# Adafruit_NeoPixel_Ring_12.net
KiCad netlist of a schematic drawn in EAGLE
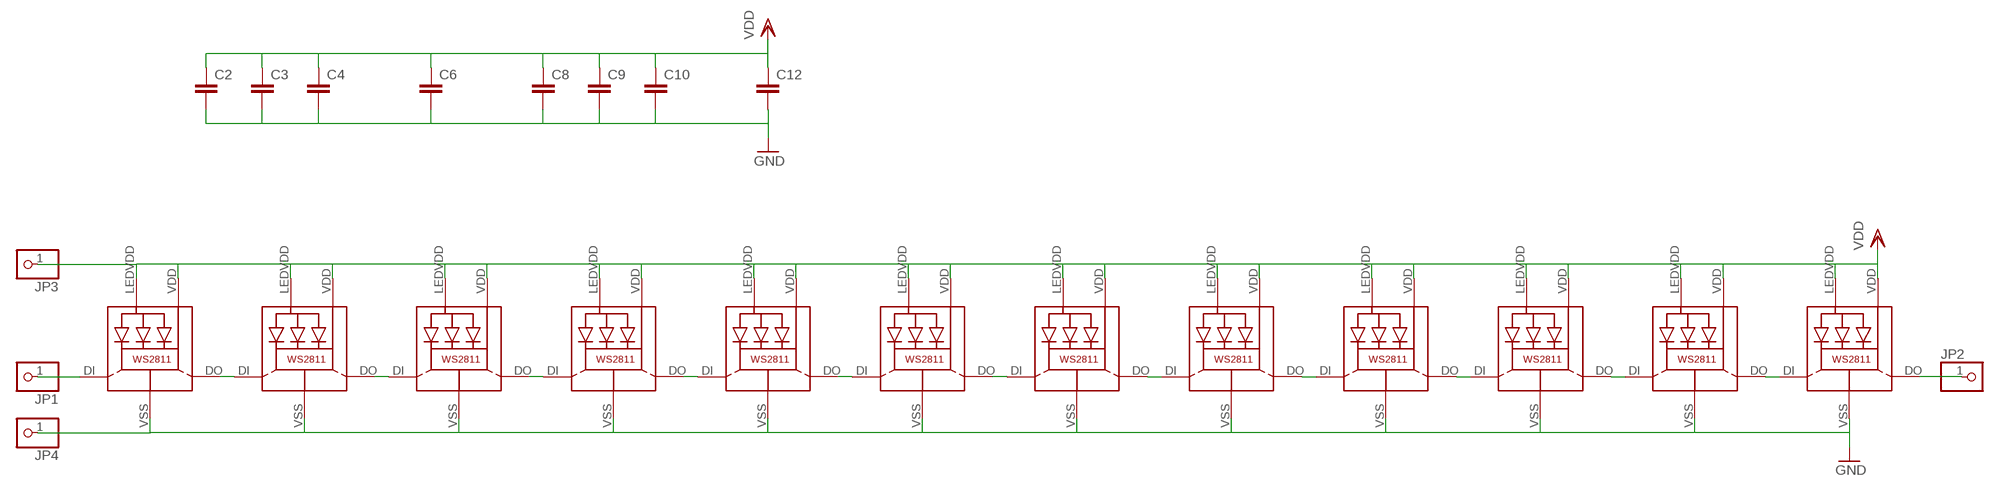
[diagram p0: schematic, sheet 1]

(export (version "E")
  (design (tool "Eeschema 10.0.6"))
  (components
    (comp (ref "C2")
      (value "C-EUC0603")
      (footprint "eagle-import:C0603")
      (libsource (lib "eagle-import") (part "C-EUC0603"))
    )
    (comp (ref "C3")
      (value "C-EUC0603")
      (footprint "eagle-import:C0603")
      (libsource (lib "eagle-import") (part "C-EUC0603"))
    )
    (comp (ref "C4")
      (value "C-EUC0603")
      (footprint "eagle-import:C0603")
      (libsource (lib "eagle-import") (part "C-EUC0603"))
    )
    (comp (ref "C6")
      (value "C-EUC0603")
      (footprint "eagle-import:C0603")
      (libsource (lib "eagle-import") (part "C-EUC0603"))
    )
    (comp (ref "C8")
      (value "C-EUC0603")
      (footprint "eagle-import:C0603")
      (libsource (lib "eagle-import") (part "C-EUC0603"))
    )
    (comp (ref "C9")
      (value "C-EUC0603")
      (footprint "eagle-import:C0603")
      (libsource (lib "eagle-import") (part "C-EUC0603"))
    )
    (comp (ref "C10")
      (value "C-EUC0603")
      (footprint "eagle-import:C0603")
      (libsource (lib "eagle-import") (part "C-EUC0603"))
    )
    (comp (ref "C12")
      (value "C-EUC0603")
      (footprint "eagle-import:C0603")
      (libsource (lib "eagle-import") (part "C-EUC0603"))
    )
    (comp (ref "JP1")
      (value "PINHD-1X1CB")
      (footprint "eagle-import:1X01-CLEANBIG")
      (libsource (lib "eagle-import") (part "PINHD-1X1CB"))
    )
    (comp (ref "JP2")
      (value "PINHD-1X1CB")
      (footprint "eagle-import:1X01-CLEANBIG")
      (libsource (lib "eagle-import") (part "PINHD-1X1CB"))
    )
    (comp (ref "JP3")
      (value "PINHD-1X1CB")
      (footprint "eagle-import:1X01-CLEANBIG")
      (libsource (lib "eagle-import") (part "PINHD-1X1CB"))
    )
    (comp (ref "JP4")
      (value "PINHD-1X1CB")
      (footprint "eagle-import:1X01-CLEANBIG")
      (libsource (lib "eagle-import") (part "PINHD-1X1CB"))
    )
    (comp (ref "LED1")
      (value "WS28115050")
      (footprint "eagle-import:WS28115050")
      (libsource (lib "eagle-import") (part "WS28115050"))
    )
    (comp (ref "LED2")
      (value "WS28115050")
      (footprint "eagle-import:WS28115050")
      (libsource (lib "eagle-import") (part "WS28115050"))
    )
    (comp (ref "LED3")
      (value "WS28115050")
      (footprint "eagle-import:WS28115050")
      (libsource (lib "eagle-import") (part "WS28115050"))
    )
    (comp (ref "LED4")
      (value "WS28115050")
      (footprint "eagle-import:WS28115050")
      (libsource (lib "eagle-import") (part "WS28115050"))
    )
    (comp (ref "LED5")
      (value "WS28115050")
      (footprint "eagle-import:WS28115050")
      (libsource (lib "eagle-import") (part "WS28115050"))
    )
    (comp (ref "LED6")
      (value "WS28115050")
      (footprint "eagle-import:WS28115050")
      (libsource (lib "eagle-import") (part "WS28115050"))
    )
    (comp (ref "LED7")
      (value "WS28115050")
      (footprint "eagle-import:WS28115050")
      (libsource (lib "eagle-import") (part "WS28115050"))
    )
    (comp (ref "LED8")
      (value "WS28115050")
      (footprint "eagle-import:WS28115050")
      (libsource (lib "eagle-import") (part "WS28115050"))
    )
    (comp (ref "LED9")
      (value "WS28115050")
      (footprint "eagle-import:WS28115050")
      (libsource (lib "eagle-import") (part "WS28115050"))
    )
    (comp (ref "LED10")
      (value "WS28115050")
      (footprint "eagle-import:WS28115050")
      (libsource (lib "eagle-import") (part "WS28115050"))
    )
    (comp (ref "LED11")
      (value "WS28115050")
      (footprint "eagle-import:WS28115050")
      (libsource (lib "eagle-import") (part "WS28115050"))
    )
    (comp (ref "LED12")
      (value "WS28115050")
      (footprint "eagle-import:WS28115050")
      (libsource (lib "eagle-import") (part "WS28115050"))
    )
  )
  (nets
    (net (code "1") (name "GND") (class "Default")
      (node (ref "C10") (pin "2") (pinfunction "2_2") (pintype "passive"))
      (node (ref "C12") (pin "2") (pinfunction "2_2") (pintype "passive"))
      (node (ref "C2") (pin "2") (pinfunction "2_2") (pintype "passive"))
      (node (ref "C3") (pin "2") (pinfunction "2_2") (pintype "passive"))
      (node (ref "C4") (pin "2") (pinfunction "2_2") (pintype "passive"))
      (node (ref "C6") (pin "2") (pinfunction "2_2") (pintype "passive"))
      (node (ref "C8") (pin "2") (pinfunction "2_2") (pintype "passive"))
      (node (ref "C9") (pin "2") (pinfunction "2_2") (pintype "passive"))
      (node (ref "JP4") (pin "1") (pinfunction "1_1") (pintype "passive"))
      (node (ref "LED1") (pin "VSS") (pinfunction "GND_VSS") (pintype "power_in"))
      (node (ref "LED10") (pin "VSS") (pinfunction "GND_VSS") (pintype "power_in"))
      (node (ref "LED11") (pin "VSS") (pinfunction "GND_VSS") (pintype "power_in"))
      (node (ref "LED12") (pin "VSS") (pinfunction "GND_VSS") (pintype "power_in"))
      (node (ref "LED2") (pin "VSS") (pinfunction "GND_VSS") (pintype "power_in"))
      (node (ref "LED3") (pin "VSS") (pinfunction "GND_VSS") (pintype "power_in"))
      (node (ref "LED4") (pin "VSS") (pinfunction "GND_VSS") (pintype "power_in"))
      (node (ref "LED5") (pin "VSS") (pinfunction "GND_VSS") (pintype "power_in"))
      (node (ref "LED6") (pin "VSS") (pinfunction "GND_VSS") (pintype "power_in"))
      (node (ref "LED7") (pin "VSS") (pinfunction "GND_VSS") (pintype "power_in"))
      (node (ref "LED8") (pin "VSS") (pinfunction "GND_VSS") (pintype "power_in"))
      (node (ref "LED9") (pin "VSS") (pinfunction "GND_VSS") (pintype "power_in"))
    )
    (net (code "2") (name "Net-(JP1-Pad1)") (class "Default")
      (node (ref "JP1") (pin "1") (pinfunction "1_1") (pintype "passive"))
      (node (ref "LED1") (pin "DI") (pinfunction "DI_DI") (pintype "input"))
    )
    (net (code "3") (name "Net-(JP2-Pad1)") (class "Default")
      (node (ref "JP2") (pin "1") (pinfunction "1_1") (pintype "passive"))
      (node (ref "LED12") (pin "DO") (pinfunction "DO_DO") (pintype "output"))
    )
    (net (code "4") (name "Net-(LED1-PadDO)") (class "Default")
      (node (ref "LED1") (pin "DO") (pinfunction "DO_DO") (pintype "output"))
      (node (ref "LED2") (pin "DI") (pinfunction "DI_DI") (pintype "input"))
    )
    (net (code "5") (name "Net-(LED2-PadDO)") (class "Default")
      (node (ref "LED2") (pin "DO") (pinfunction "DO_DO") (pintype "output"))
      (node (ref "LED3") (pin "DI") (pinfunction "DI_DI") (pintype "input"))
    )
    (net (code "6") (name "Net-(LED3-PadDO)") (class "Default")
      (node (ref "LED3") (pin "DO") (pinfunction "DO_DO") (pintype "output"))
      (node (ref "LED4") (pin "DI") (pinfunction "DI_DI") (pintype "input"))
    )
    (net (code "7") (name "Net-(LED4-PadDO)") (class "Default")
      (node (ref "LED4") (pin "DO") (pinfunction "DO_DO") (pintype "output"))
      (node (ref "LED5") (pin "DI") (pinfunction "DI_DI") (pintype "input"))
    )
    (net (code "8") (name "Net-(LED5-PadDO)") (class "Default")
      (node (ref "LED5") (pin "DO") (pinfunction "DO_DO") (pintype "output"))
      (node (ref "LED6") (pin "DI") (pinfunction "DI_DI") (pintype "input"))
    )
    (net (code "9") (name "Net-(LED6-PadDO)") (class "Default")
      (node (ref "LED6") (pin "DO") (pinfunction "DO_DO") (pintype "output"))
      (node (ref "LED7") (pin "DI") (pinfunction "DI_DI") (pintype "input"))
    )
    (net (code "10") (name "Net-(LED7-PadDO)") (class "Default")
      (node (ref "LED7") (pin "DO") (pinfunction "DO_DO") (pintype "output"))
      (node (ref "LED8") (pin "DI") (pinfunction "DI_DI") (pintype "input"))
    )
    (net (code "11") (name "Net-(LED8-PadDO)") (class "Default")
      (node (ref "LED8") (pin "DO") (pinfunction "DO_DO") (pintype "output"))
      (node (ref "LED9") (pin "DI") (pinfunction "DI_DI") (pintype "input"))
    )
    (net (code "12") (name "Net-(LED10-PadDI)") (class "Default")
      (node (ref "LED10") (pin "DI") (pinfunction "DI_DI") (pintype "input"))
      (node (ref "LED9") (pin "DO") (pinfunction "DO_DO") (pintype "output"))
    )
    (net (code "13") (name "Net-(LED10-PadDO)") (class "Default")
      (node (ref "LED10") (pin "DO") (pinfunction "DO_DO") (pintype "output"))
      (node (ref "LED11") (pin "DI") (pinfunction "DI_DI") (pintype "input"))
    )
    (net (code "14") (name "Net-(LED11-PadDO)") (class "Default")
      (node (ref "LED11") (pin "DO") (pinfunction "DO_DO") (pintype "output"))
      (node (ref "LED12") (pin "DI") (pinfunction "DI_DI") (pintype "input"))
    )
    (net (code "15") (name "VDD") (class "Default")
      (node (ref "C10") (pin "1") (pinfunction "1_1") (pintype "passive"))
      (node (ref "C12") (pin "1") (pinfunction "1_1") (pintype "passive"))
      (node (ref "C2") (pin "1") (pinfunction "1_1") (pintype "passive"))
      (node (ref "C3") (pin "1") (pinfunction "1_1") (pintype "passive"))
      (node (ref "C4") (pin "1") (pinfunction "1_1") (pintype "passive"))
      (node (ref "C6") (pin "1") (pinfunction "1_1") (pintype "passive"))
      (node (ref "C8") (pin "1") (pinfunction "1_1") (pintype "passive"))
      (node (ref "C9") (pin "1") (pinfunction "1_1") (pintype "passive"))
      (node (ref "JP3") (pin "1") (pinfunction "1_1") (pintype "passive"))
      (node (ref "LED1") (pin "LEDVDD") (pinfunction "LEDVDD_LEDVDD") (pintype "power_in"))
      (node (ref "LED1") (pin "VDD") (pinfunction "VDD_VDD") (pintype "power_in"))
      (node (ref "LED10") (pin "LEDVDD") (pinfunction "LEDVDD_LEDVDD") (pintype "power_in"))
      (node (ref "LED10") (pin "VDD") (pinfunction "VDD_VDD") (pintype "power_in"))
      (node (ref "LED11") (pin "LEDVDD") (pinfunction "LEDVDD_LEDVDD") (pintype "power_in"))
      (node (ref "LED11") (pin "VDD") (pinfunction "VDD_VDD") (pintype "power_in"))
      (node (ref "LED12") (pin "LEDVDD") (pinfunction "LEDVDD_LEDVDD") (pintype "power_in"))
      (node (ref "LED12") (pin "VDD") (pinfunction "VDD_VDD") (pintype "power_in"))
      (node (ref "LED2") (pin "LEDVDD") (pinfunction "LEDVDD_LEDVDD") (pintype "power_in"))
      (node (ref "LED2") (pin "VDD") (pinfunction "VDD_VDD") (pintype "power_in"))
      (node (ref "LED3") (pin "LEDVDD") (pinfunction "LEDVDD_LEDVDD") (pintype "power_in"))
      (node (ref "LED3") (pin "VDD") (pinfunction "VDD_VDD") (pintype "power_in"))
      (node (ref "LED4") (pin "LEDVDD") (pinfunction "LEDVDD_LEDVDD") (pintype "power_in"))
      (node (ref "LED4") (pin "VDD") (pinfunction "VDD_VDD") (pintype "power_in"))
      (node (ref "LED5") (pin "LEDVDD") (pinfunction "LEDVDD_LEDVDD") (pintype "power_in"))
      (node (ref "LED5") (pin "VDD") (pinfunction "VDD_VDD") (pintype "power_in"))
      (node (ref "LED6") (pin "LEDVDD") (pinfunction "LEDVDD_LEDVDD") (pintype "power_in"))
      (node (ref "LED6") (pin "VDD") (pinfunction "VDD_VDD") (pintype "power_in"))
      (node (ref "LED7") (pin "LEDVDD") (pinfunction "LEDVDD_LEDVDD") (pintype "power_in"))
      (node (ref "LED7") (pin "VDD") (pinfunction "VDD_VDD") (pintype "power_in"))
      (node (ref "LED8") (pin "LEDVDD") (pinfunction "LEDVDD_LEDVDD") (pintype "power_in"))
      (node (ref "LED8") (pin "VDD") (pinfunction "VDD_VDD") (pintype "power_in"))
      (node (ref "LED9") (pin "LEDVDD") (pinfunction "LEDVDD_LEDVDD") (pintype "power_in"))
      (node (ref "LED9") (pin "VDD") (pinfunction "VDD_VDD") (pintype "power_in"))
    )
  )
)
